# ww-impedance-matching-circuit.net
KiCad netlist of a schematic drawn in EAGLE
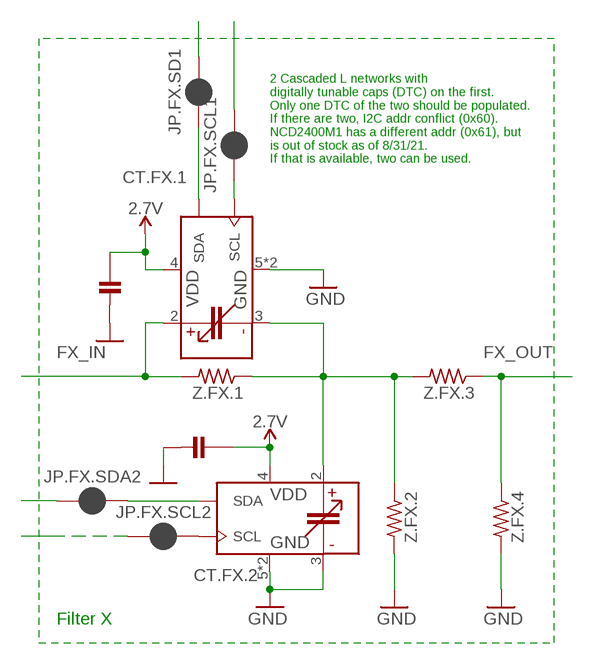
[diagram p0: schematic, sheet 1]

(export (version "E")
  (design (tool "Eeschema 10.0.6"))
  (components
    (comp (ref "C1")
      (value "C-0603")
      (footprint "eagle-import:C0603")
      (fields (field (name "MANUFACTURER") "Kemet") (field (name "VOLTAGE") "6.3V"))
      (libsource (lib "eagle-import") (part "C-0603"))
    )
    (comp (ref "C2")
      (value "C-0603")
      (footprint "eagle-import:C0603")
      (fields (field (name "MANUFACTURER") "Kemet") (field (name "VOLTAGE") "6.3V"))
      (libsource (lib "eagle-import") (part "C-0603"))
    )
    (comp (ref "CT.FX.1")
      (value "TUNABLE_CAP_NCD2400MTR")
      (footprint "eagle-import:DFN-6_NCD2400M")
      (fields (field (name "MP") "NCD2400M"))
      (libsource (lib "eagle-import") (part "TUNABLE_CAP_NCD2400MTR"))
    )
    (comp (ref "CT.FX.2")
      (value "TUNABLE_CAP_NCD2400MTR")
      (footprint "eagle-import:DFN-6_NCD2400M")
      (fields (field (name "MP") "NCD2400M"))
      (libsource (lib "eagle-import") (part "TUNABLE_CAP_NCD2400MTR"))
    )
    (comp (ref "JP.FX.SCL1")
      (value "JUMPER-SMT_2_NC_PASTE_NO-SILK")
      (footprint "eagle-import:SMT-JUMPER_2_NC_PASTE_NO-SILK")
      (libsource (lib "eagle-import") (part "JUMPER-SMT_2_NC_PASTE_NO-SILK"))
    )
    (comp (ref "JP.FX.SCL2")
      (value "JUMPER-SMT_2_NC_PASTE_NO-SILK")
      (footprint "eagle-import:SMT-JUMPER_2_NC_PASTE_NO-SILK")
      (libsource (lib "eagle-import") (part "JUMPER-SMT_2_NC_PASTE_NO-SILK"))
    )
    (comp (ref "JP.FX.SD1")
      (value "JUMPER-SMT_2_NC_PASTE_NO-SILK")
      (footprint "eagle-import:SMT-JUMPER_2_NC_PASTE_NO-SILK")
      (libsource (lib "eagle-import") (part "JUMPER-SMT_2_NC_PASTE_NO-SILK"))
    )
    (comp (ref "JP.FX.SDA2")
      (value "JUMPER-SMT_2_NC_PASTE_NO-SILK")
      (footprint "eagle-import:SMT-JUMPER_2_NC_PASTE_NO-SILK")
      (libsource (lib "eagle-import") (part "JUMPER-SMT_2_NC_PASTE_NO-SILK"))
    )
    (comp (ref "Z.FX.1")
      (value "R-0603")
      (footprint "eagle-import:R0603")
      (fields (field (name "MANUFACTURER") "Panasonic"))
      (libsource (lib "eagle-import") (part "R-0603"))
    )
    (comp (ref "Z.FX.2")
      (value "R-0603")
      (footprint "eagle-import:R0603")
      (fields (field (name "MANUFACTURER") "Panasonic"))
      (libsource (lib "eagle-import") (part "R-0603"))
    )
    (comp (ref "Z.FX.3")
      (value "R-0603")
      (footprint "eagle-import:R0603")
      (fields (field (name "MANUFACTURER") "Panasonic"))
      (libsource (lib "eagle-import") (part "R-0603"))
    )
    (comp (ref "Z.FX.4")
      (value "R-0603")
      (footprint "eagle-import:R0603")
      (fields (field (name "MANUFACTURER") "Panasonic"))
      (libsource (lib "eagle-import") (part "R-0603"))
    )
  )
  (nets
    (net (code "1") (name "/FX_IN") (class "Default")
      (node (ref "CT.FX.1") (pin "2") (pinfunction "C+_2") (pintype "passive"))
      (node (ref "Z.FX.1") (pin "2") (pinfunction "2_2") (pintype "passive"))
    )
    (net (code "2") (name "/FX_OUT") (class "Default")
      (node (ref "Z.FX.3") (pin "1") (pinfunction "1_1") (pintype "passive"))
      (node (ref "Z.FX.4") (pin "1") (pinfunction "1_1") (pintype "passive"))
    )
    (net (code "3") (name "2.7V") (class "Default")
      (node (ref "C1") (pin "1") (pinfunction "1_1") (pintype "passive"))
      (node (ref "C2") (pin "1") (pinfunction "1_1") (pintype "passive"))
      (node (ref "CT.FX.1") (pin "4") (pinfunction "VDD_4") (pintype "bidirectional"))
      (node (ref "CT.FX.2") (pin "4") (pinfunction "VDD_4") (pintype "bidirectional"))
    )
    (net (code "4") (name "GND") (class "Default")
      (node (ref "C1") (pin "2") (pinfunction "2_2") (pintype "passive"))
      (node (ref "C2") (pin "2") (pinfunction "2_2") (pintype "passive"))
      (node (ref "CT.FX.1") (pin "5") (pinfunction "GND_5") (pintype "power_in"))
      (node (ref "CT.FX.1") (pin "7") (pinfunction "GND_7") (pintype "power_in"))
      (node (ref "CT.FX.2") (pin "3") (pinfunction "C-_3") (pintype "passive"))
      (node (ref "CT.FX.2") (pin "5") (pinfunction "GND_5") (pintype "power_in"))
      (node (ref "CT.FX.2") (pin "7") (pinfunction "GND_7") (pintype "power_in"))
      (node (ref "Z.FX.2") (pin "2") (pinfunction "2_2") (pintype "passive"))
      (node (ref "Z.FX.4") (pin "2") (pinfunction "2_2") (pintype "passive"))
    )
    (net (code "5") (name "Net-(CT.FX.1-C-)") (class "Default")
      (node (ref "CT.FX.1") (pin "3") (pinfunction "C-_3") (pintype "passive"))
      (node (ref "CT.FX.2") (pin "2") (pinfunction "C+_2") (pintype "passive"))
      (node (ref "Z.FX.1") (pin "1") (pinfunction "1_1") (pintype "passive"))
      (node (ref "Z.FX.2") (pin "1") (pinfunction "1_1") (pintype "passive"))
      (node (ref "Z.FX.3") (pin "2") (pinfunction "2_2") (pintype "passive"))
    )
    (net (code "6") (name "Net-(CT.FX.1-SCL)") (class "Default")
      (node (ref "CT.FX.1") (pin "6") (pinfunction "SCL_6") (pintype "bidirectional"))
      (node (ref "JP.FX.SCL1") (pin "2") (pinfunction "2_2") (pintype "passive"))
    )
    (net (code "7") (name "Net-(CT.FX.1-SDA)") (class "Default")
      (node (ref "CT.FX.1") (pin "1") (pinfunction "SDA_1") (pintype "bidirectional"))
      (node (ref "JP.FX.SD1") (pin "2") (pinfunction "2_2") (pintype "passive"))
    )
    (net (code "8") (name "Net-(CT.FX.2-SCL)") (class "Default")
      (node (ref "CT.FX.2") (pin "6") (pinfunction "SCL_6") (pintype "bidirectional"))
      (node (ref "JP.FX.SCL2") (pin "1") (pinfunction "1_1") (pintype "passive"))
    )
    (net (code "9") (name "Net-(CT.FX.2-SDA)") (class "Default")
      (node (ref "CT.FX.2") (pin "1") (pinfunction "SDA_1") (pintype "bidirectional"))
      (node (ref "JP.FX.SDA2") (pin "1") (pinfunction "1_1") (pintype "passive"))
    )
    (net (code "10") (name "unconnected-(JP.FX.SCL1-Pad1)") (class "Default")
      (node (ref "JP.FX.SCL1") (pin "1") (pinfunction "1_1") (pintype "passive"))
    )
    (net (code "11") (name "unconnected-(JP.FX.SCL2-Pad2)") (class "Default")
      (node (ref "JP.FX.SCL2") (pin "2") (pinfunction "2_2") (pintype "passive"))
    )
    (net (code "12") (name "unconnected-(JP.FX.SD1-Pad1)") (class "Default")
      (node (ref "JP.FX.SD1") (pin "1") (pinfunction "1_1") (pintype "passive"))
    )
    (net (code "13") (name "unconnected-(JP.FX.SDA2-Pad2)") (class "Default")
      (node (ref "JP.FX.SDA2") (pin "2") (pinfunction "2_2") (pintype "passive"))
    )
  )
)
